# motordrive1.net
KiCad netlist of a schematic drawn in EAGLE
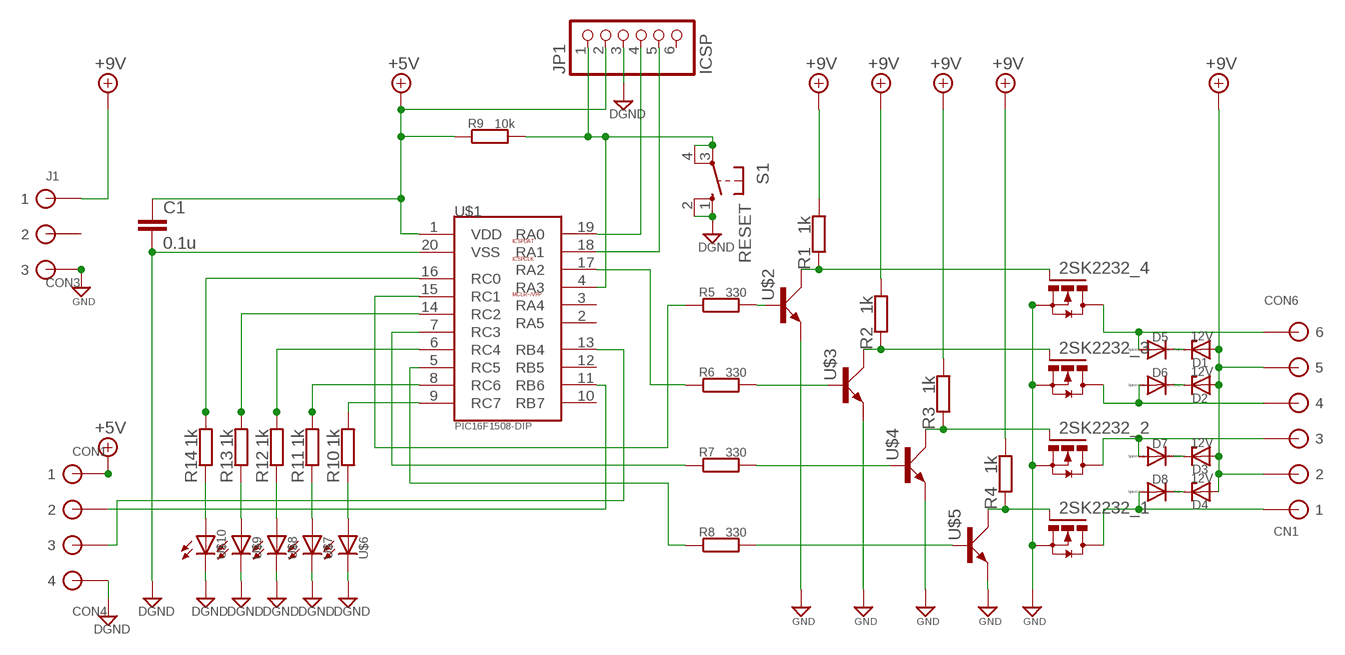
[diagram p0: schematic, sheet 1]

(export (version "E")
  (design (tool "Eeschema 10.0.6"))
  (components
    (comp (ref "2SK2232_1")
      (value "TO-220(MOS-FET_N)")
      (footprint "eagle-import:TO-220")
      (libsource (lib "eagle-import") (part "TO-220(MOS-FET_N)"))
    )
    (comp (ref "2SK2232_2")
      (value "TO-220(MOS-FET_N)")
      (footprint "eagle-import:TO-220")
      (libsource (lib "eagle-import") (part "TO-220(MOS-FET_N)"))
    )
    (comp (ref "2SK2232_3")
      (value "TO-220(MOS-FET_N)")
      (footprint "eagle-import:TO-220")
      (libsource (lib "eagle-import") (part "TO-220(MOS-FET_N)"))
    )
    (comp (ref "2SK2232_4")
      (value "TO-220(MOS-FET_N)")
      (footprint "eagle-import:TO-220")
      (libsource (lib "eagle-import") (part "TO-220(MOS-FET_N)"))
    )
    (comp (ref "C1")
      (value "0.1u")
      (footprint "eagle-import:C050-024X044")
      (libsource (lib "eagle-import") (part "コンデンサ(小型極性無し)050-024X044"))
    )
    (comp (ref "CN1")
      (value "CON6")
      (footprint "eagle-import:CON6")
      (libsource (lib "eagle-import") (part "CON6"))
    )
    (comp (ref "CON1")
      (value "CON4")
      (footprint "eagle-import:CON4")
      (libsource (lib "eagle-import") (part "CON4"))
    )
    (comp (ref "D1")
      (value "12V")
      (footprint "eagle-import:DO41Z(D=3)")
      (libsource (lib "eagle-import") (part "(汎用)ツェナーダイオードD=3"))
    )
    (comp (ref "D2")
      (value "12V")
      (footprint "eagle-import:DO41Z(D=3)")
      (libsource (lib "eagle-import") (part "(汎用)ツェナーダイオードD=3"))
    )
    (comp (ref "D3")
      (value "12V")
      (footprint "eagle-import:DO41Z(D=3)")
      (libsource (lib "eagle-import") (part "(汎用)ツェナーダイオードD=3"))
    )
    (comp (ref "D4")
      (value "12V")
      (footprint "eagle-import:DO41Z(D=3)")
      (libsource (lib "eagle-import") (part "(汎用)ツェナーダイオードD=3"))
    )
    (comp (ref "D5")
      (value "(汎用)D=3")
      (footprint "eagle-import:DO41(D=3)")
      (libsource (lib "eagle-import") (part "(汎用)D=3"))
    )
    (comp (ref "D6")
      (value "(汎用)D=3")
      (footprint "eagle-import:DO41(D=3)")
      (libsource (lib "eagle-import") (part "(汎用)D=3"))
    )
    (comp (ref "D7")
      (value "(汎用)D=3")
      (footprint "eagle-import:DO41(D=3)")
      (libsource (lib "eagle-import") (part "(汎用)D=3"))
    )
    (comp (ref "D8")
      (value "(汎用)D=3")
      (footprint "eagle-import:DO41(D=3)")
      (libsource (lib "eagle-import") (part "(汎用)D=3"))
    )
    (comp (ref "J1")
      (value "CON3")
      (footprint "eagle-import:CON3")
      (libsource (lib "eagle-import") (part "CON3"))
    )
    (comp (ref "JP1")
      (value "ICSP")
      (footprint "eagle-import:1X06")
      (libsource (lib "eagle-import") (part "PINHD-1X6"))
    )
    (comp (ref "R1")
      (value "1k")
      (footprint "eagle-import:0207_10")
      (libsource (lib "eagle-import") (part "抵抗(新JIS)0207/10"))
    )
    (comp (ref "R2")
      (value "1k")
      (footprint "eagle-import:0207_10")
      (libsource (lib "eagle-import") (part "抵抗(新JIS)0207/10"))
    )
    (comp (ref "R3")
      (value "1k")
      (footprint "eagle-import:0207_10")
      (libsource (lib "eagle-import") (part "抵抗(新JIS)0207/10"))
    )
    (comp (ref "R4")
      (value "1k")
      (footprint "eagle-import:0207_10")
      (libsource (lib "eagle-import") (part "抵抗(新JIS)0207/10"))
    )
    (comp (ref "R5")
      (value "330")
      (footprint "eagle-import:1_4W-H4_(0207_10)")
      (libsource (lib "eagle-import") (part "抵抗0207/10"))
    )
    (comp (ref "R6")
      (value "330")
      (footprint "eagle-import:1_4W-H4_(0207_10)")
      (libsource (lib "eagle-import") (part "抵抗0207/10"))
    )
    (comp (ref "R7")
      (value "330")
      (footprint "eagle-import:1_4W-H4_(0207_10)")
      (libsource (lib "eagle-import") (part "抵抗0207/10"))
    )
    (comp (ref "R8")
      (value "330")
      (footprint "eagle-import:1_4W-H4_(0207_10)")
      (libsource (lib "eagle-import") (part "抵抗0207/10"))
    )
    (comp (ref "R9")
      (value "10k")
      (footprint "eagle-import:1_4W-H4_(0207_10)")
      (libsource (lib "eagle-import") (part "抵抗0207/10"))
    )
    (comp (ref "R10")
      (value "1k")
      (footprint "eagle-import:0207_10")
      (libsource (lib "eagle-import") (part "抵抗(新JIS)0207/10"))
    )
    (comp (ref "R11")
      (value "1k")
      (footprint "eagle-import:0207_10")
      (libsource (lib "eagle-import") (part "抵抗(新JIS)0207/10"))
    )
    (comp (ref "R12")
      (value "1k")
      (footprint "eagle-import:0207_10")
      (libsource (lib "eagle-import") (part "抵抗(新JIS)0207/10"))
    )
    (comp (ref "R13")
      (value "1k")
      (footprint "eagle-import:0207_10")
      (libsource (lib "eagle-import") (part "抵抗(新JIS)0207/10"))
    )
    (comp (ref "R14")
      (value "1k")
      (footprint "eagle-import:0207_10")
      (libsource (lib "eagle-import") (part "抵抗(新JIS)0207/10"))
    )
    (comp (ref "S1")
      (value "RESET")
      (footprint "eagle-import:B3F-10XX")
      (fields (field (name "MPN") "B3F-1000"))
      (libsource (lib "eagle-import") (part "ノーマル4ピンタクトスイッチ"))
    )
    (comp (ref "U$1")
      (value "PIC16F1508-DIP")
      (footprint "eagle-import:DIP254P762X533-20")
      (libsource (lib "eagle-import") (part "PIC16F1508-DIP"))
    )
    (comp (ref "U$2")
      (value "TO-92(TRANSISTER_NPN)")
      (footprint "eagle-import:TO-92")
      (libsource (lib "eagle-import") (part "TO-92(TRANSISTER_NPN)"))
    )
    (comp (ref "U$3")
      (value "TO-92(TRANSISTER_NPN)")
      (footprint "eagle-import:TO-92")
      (libsource (lib "eagle-import") (part "TO-92(TRANSISTER_NPN)"))
    )
    (comp (ref "U$4")
      (value "TO-92(TRANSISTER_NPN)")
      (footprint "eagle-import:TO-92")
      (libsource (lib "eagle-import") (part "TO-92(TRANSISTER_NPN)"))
    )
    (comp (ref "U$5")
      (value "TO-92(TRANSISTER_NPN)")
      (footprint "eagle-import:TO-92")
      (libsource (lib "eagle-import") (part "TO-92(TRANSISTER_NPN)"))
    )
    (comp (ref "U$6")
      (value "LED(砲弾型)5")
      (footprint "eagle-import:LED5MM")
      (libsource (lib "eagle-import") (part "LED(砲弾型)5"))
    )
    (comp (ref "U$7")
      (value "LED(砲弾型)5")
      (footprint "eagle-import:LED5MM")
      (libsource (lib "eagle-import") (part "LED(砲弾型)5"))
    )
    (comp (ref "U$8")
      (value "LED(砲弾型)5")
      (footprint "eagle-import:LED5MM")
      (libsource (lib "eagle-import") (part "LED(砲弾型)5"))
    )
    (comp (ref "U$9")
      (value "LED(砲弾型)5")
      (footprint "eagle-import:LED5MM")
      (libsource (lib "eagle-import") (part "LED(砲弾型)5"))
    )
    (comp (ref "U$10")
      (value "LED(砲弾型)5")
      (footprint "eagle-import:LED5MM")
      (libsource (lib "eagle-import") (part "LED(砲弾型)5"))
    )
  )
  (nets
    (net (code "1") (name "+5V") (class "Default")
      (node (ref "C1") (pin "1") (pinfunction "1_1") (pintype "passive"))
      (node (ref "CON1") (pin "P$1") (pinfunction "1_P$1") (pintype "bidirectional"))
      (node (ref "JP1") (pin "2") (pinfunction "2_2") (pintype "passive"))
      (node (ref "R9") (pin "1") (pinfunction "1_1") (pintype "passive"))
      (node (ref "U$1") (pin "1") (pinfunction "VDD_1") (pintype "bidirectional"))
    )
    (net (code "2") (name "+9V") (class "Default")
      (node (ref "CN1") (pin "P$2") (pinfunction "2_P$2") (pintype "bidirectional"))
      (node (ref "CN1") (pin "P$5") (pinfunction "5_P$5") (pintype "bidirectional"))
      (node (ref "D1") (pin "A") (pinfunction "A_A") (pintype "passive"))
      (node (ref "D2") (pin "A") (pinfunction "A_A") (pintype "passive"))
      (node (ref "D3") (pin "A") (pinfunction "A_A") (pintype "passive"))
      (node (ref "D4") (pin "A") (pinfunction "A_A") (pintype "passive"))
      (node (ref "J1") (pin "P$1") (pinfunction "1_P$1") (pintype "bidirectional"))
      (node (ref "R1") (pin "2") (pinfunction "2_2") (pintype "passive"))
      (node (ref "R2") (pin "2") (pinfunction "2_2") (pintype "passive"))
      (node (ref "R3") (pin "2") (pinfunction "2_2") (pintype "passive"))
      (node (ref "R4") (pin "2") (pinfunction "2_2") (pintype "passive"))
    )
    (net (code "3") (name "DGND") (class "Default")
      (node (ref "C1") (pin "2") (pinfunction "2_2") (pintype "passive"))
      (node (ref "CON1") (pin "P$4") (pinfunction "4_P$4") (pintype "bidirectional"))
      (node (ref "JP1") (pin "3") (pinfunction "3_3") (pintype "passive"))
      (node (ref "S1") (pin "1") (pinfunction "S_1") (pintype "passive"))
      (node (ref "S1") (pin "2") (pinfunction "S1_2") (pintype "passive"))
      (node (ref "U$1") (pin "20") (pinfunction "VSS_20") (pintype "bidirectional"))
      (node (ref "U$10") (pin "K") (pinfunction "K_K") (pintype "passive"))
      (node (ref "U$6") (pin "K") (pinfunction "K_K") (pintype "passive"))
      (node (ref "U$7") (pin "K") (pinfunction "K_K") (pintype "passive"))
      (node (ref "U$8") (pin "K") (pinfunction "K_K") (pintype "passive"))
      (node (ref "U$9") (pin "K") (pinfunction "K_K") (pintype "passive"))
    )
    (net (code "4") (name "GND") (class "Default")
      (node (ref "2SK2232_1") (pin "3") (pinfunction "S_3") (pintype "passive"))
      (node (ref "2SK2232_2") (pin "3") (pinfunction "S_3") (pintype "passive"))
      (node (ref "2SK2232_3") (pin "3") (pinfunction "S_3") (pintype "passive"))
      (node (ref "2SK2232_4") (pin "3") (pinfunction "S_3") (pintype "passive"))
      (node (ref "J1") (pin "P$3") (pinfunction "3_P$3") (pintype "bidirectional"))
      (node (ref "U$2") (pin "1") (pinfunction "E_1") (pintype "passive"))
      (node (ref "U$3") (pin "1") (pinfunction "E_1") (pintype "passive"))
      (node (ref "U$4") (pin "1") (pinfunction "E_1") (pintype "passive"))
      (node (ref "U$5") (pin "1") (pinfunction "E_1") (pintype "passive"))
    )
    (net (code "5") (name "Net-(2SK2232_1-D)") (class "Default")
      (node (ref "2SK2232_1") (pin "2") (pinfunction "D_2") (pintype "passive"))
      (node (ref "CN1") (pin "P$1") (pinfunction "1_P$1") (pintype "bidirectional"))
      (node (ref "D8") (pin "A") (pinfunction "A_A") (pintype "passive"))
    )
    (net (code "6") (name "Net-(2SK2232_1-G)") (class "Default")
      (node (ref "2SK2232_1") (pin "1") (pinfunction "G_1") (pintype "passive"))
      (node (ref "R4") (pin "1") (pinfunction "1_1") (pintype "passive"))
      (node (ref "U$5") (pin "2") (pinfunction "C_2") (pintype "passive"))
    )
    (net (code "7") (name "Net-(2SK2232_2-D)") (class "Default")
      (node (ref "2SK2232_2") (pin "2") (pinfunction "D_2") (pintype "passive"))
      (node (ref "CN1") (pin "P$3") (pinfunction "3_P$3") (pintype "bidirectional"))
      (node (ref "D7") (pin "A") (pinfunction "A_A") (pintype "passive"))
    )
    (net (code "8") (name "Net-(2SK2232_2-G)") (class "Default")
      (node (ref "2SK2232_2") (pin "1") (pinfunction "G_1") (pintype "passive"))
      (node (ref "R3") (pin "1") (pinfunction "1_1") (pintype "passive"))
      (node (ref "U$4") (pin "2") (pinfunction "C_2") (pintype "passive"))
    )
    (net (code "9") (name "Net-(2SK2232_3-D)") (class "Default")
      (node (ref "2SK2232_3") (pin "2") (pinfunction "D_2") (pintype "passive"))
      (node (ref "CN1") (pin "P$4") (pinfunction "4_P$4") (pintype "bidirectional"))
      (node (ref "D6") (pin "A") (pinfunction "A_A") (pintype "passive"))
    )
    (net (code "10") (name "Net-(2SK2232_3-G)") (class "Default")
      (node (ref "2SK2232_3") (pin "1") (pinfunction "G_1") (pintype "passive"))
      (node (ref "R2") (pin "1") (pinfunction "1_1") (pintype "passive"))
      (node (ref "U$3") (pin "2") (pinfunction "C_2") (pintype "passive"))
    )
    (net (code "11") (name "Net-(2SK2232_4-D)") (class "Default")
      (node (ref "2SK2232_4") (pin "2") (pinfunction "D_2") (pintype "passive"))
      (node (ref "CN1") (pin "P$6") (pinfunction "6_P$6") (pintype "bidirectional"))
      (node (ref "D5") (pin "A") (pinfunction "A_A") (pintype "passive"))
    )
    (net (code "12") (name "Net-(2SK2232_4-G)") (class "Default")
      (node (ref "2SK2232_4") (pin "1") (pinfunction "G_1") (pintype "passive"))
      (node (ref "R1") (pin "1") (pinfunction "1_1") (pintype "passive"))
      (node (ref "U$2") (pin "2") (pinfunction "C_2") (pintype "passive"))
    )
    (net (code "13") (name "Net-(CON1-2)") (class "Default")
      (node (ref "CON1") (pin "P$2") (pinfunction "2_P$2") (pintype "bidirectional"))
      (node (ref "U$1") (pin "11") (pinfunction "RB6_11") (pintype "bidirectional"))
    )
    (net (code "14") (name "Net-(CON1-3)") (class "Default")
      (node (ref "CON1") (pin "P$3") (pinfunction "3_P$3") (pintype "bidirectional"))
      (node (ref "U$1") (pin "13") (pinfunction "RB4_13") (pintype "bidirectional"))
    )
    (net (code "15") (name "Net-(D1-PadC)") (class "Default")
      (node (ref "D1") (pin "C") (pinfunction "C_C") (pintype "passive"))
      (node (ref "D5") (pin "C") (pinfunction "C_C") (pintype "passive"))
    )
    (net (code "16") (name "Net-(D2-PadC)") (class "Default")
      (node (ref "D2") (pin "C") (pinfunction "C_C") (pintype "passive"))
      (node (ref "D6") (pin "C") (pinfunction "C_C") (pintype "passive"))
    )
    (net (code "17") (name "Net-(D3-PadC)") (class "Default")
      (node (ref "D3") (pin "C") (pinfunction "C_C") (pintype "passive"))
      (node (ref "D7") (pin "C") (pinfunction "C_C") (pintype "passive"))
    )
    (net (code "18") (name "Net-(D4-PadC)") (class "Default")
      (node (ref "D4") (pin "C") (pinfunction "C_C") (pintype "passive"))
      (node (ref "D8") (pin "C") (pinfunction "C_C") (pintype "passive"))
    )
    (net (code "19") (name "Net-(R10-Pad1)") (class "Default")
      (node (ref "R10") (pin "1") (pinfunction "1_1") (pintype "passive"))
      (node (ref "U$6") (pin "A") (pinfunction "A_A") (pintype "passive"))
    )
    (net (code "20") (name "Net-(R11-Pad1)") (class "Default")
      (node (ref "R11") (pin "1") (pinfunction "1_1") (pintype "passive"))
      (node (ref "U$7") (pin "A") (pinfunction "A_A") (pintype "passive"))
    )
    (net (code "21") (name "Net-(R12-Pad1)") (class "Default")
      (node (ref "R12") (pin "1") (pinfunction "1_1") (pintype "passive"))
      (node (ref "U$8") (pin "A") (pinfunction "A_A") (pintype "passive"))
    )
    (net (code "22") (name "Net-(R13-Pad1)") (class "Default")
      (node (ref "R13") (pin "1") (pinfunction "1_1") (pintype "passive"))
      (node (ref "U$9") (pin "A") (pinfunction "A_A") (pintype "passive"))
    )
    (net (code "23") (name "Net-(R14-Pad1)") (class "Default")
      (node (ref "R14") (pin "1") (pinfunction "1_1") (pintype "passive"))
      (node (ref "U$10") (pin "A") (pinfunction "A_A") (pintype "passive"))
    )
    (net (code "24") (name "Net-(S1-P)") (class "Default")
      (node (ref "JP1") (pin "1") (pinfunction "1_1") (pintype "passive"))
      (node (ref "R9") (pin "2") (pinfunction "2_2") (pintype "passive"))
      (node (ref "S1") (pin "3") (pinfunction "P_3") (pintype "passive"))
      (node (ref "S1") (pin "4") (pinfunction "P1_4") (pintype "passive"))
      (node (ref "U$1") (pin "4") (pinfunction "RA3_4") (pintype "bidirectional"))
    )
    (net (code "25") (name "Net-(U$1-RA0)") (class "Default")
      (node (ref "JP1") (pin "4") (pinfunction "4_4") (pintype "passive"))
      (node (ref "U$1") (pin "19") (pinfunction "RA0_19") (pintype "bidirectional"))
    )
    (net (code "26") (name "Net-(U$1-RA1)") (class "Default")
      (node (ref "JP1") (pin "5") (pinfunction "5_5") (pintype "passive"))
      (node (ref "U$1") (pin "18") (pinfunction "RA1_18") (pintype "bidirectional"))
    )
    (net (code "27") (name "Net-(U$1-RA2)") (class "Default")
      (node (ref "R6") (pin "1") (pinfunction "1_1") (pintype "passive"))
      (node (ref "U$1") (pin "17") (pinfunction "RA2_17") (pintype "bidirectional"))
    )
    (net (code "28") (name "Net-(U$1-RC0)") (class "Default")
      (node (ref "R14") (pin "2") (pinfunction "2_2") (pintype "passive"))
      (node (ref "U$1") (pin "16") (pinfunction "RC0_16") (pintype "bidirectional"))
    )
    (net (code "29") (name "Net-(U$1-RC1)") (class "Default")
      (node (ref "R5") (pin "1") (pinfunction "1_1") (pintype "passive"))
      (node (ref "U$1") (pin "15") (pinfunction "RC1_15") (pintype "bidirectional"))
    )
    (net (code "30") (name "Net-(U$1-RC2)") (class "Default")
      (node (ref "R13") (pin "2") (pinfunction "2_2") (pintype "passive"))
      (node (ref "U$1") (pin "14") (pinfunction "RC2_14") (pintype "bidirectional"))
    )
    (net (code "31") (name "Net-(U$1-RC3)") (class "Default")
      (node (ref "R7") (pin "1") (pinfunction "1_1") (pintype "passive"))
      (node (ref "U$1") (pin "7") (pinfunction "RC3_7") (pintype "bidirectional"))
    )
    (net (code "32") (name "Net-(U$1-RC4)") (class "Default")
      (node (ref "R12") (pin "2") (pinfunction "2_2") (pintype "passive"))
      (node (ref "U$1") (pin "6") (pinfunction "RC4_6") (pintype "bidirectional"))
    )
    (net (code "33") (name "Net-(U$1-RC5)") (class "Default")
      (node (ref "R8") (pin "1") (pinfunction "1_1") (pintype "passive"))
      (node (ref "U$1") (pin "5") (pinfunction "RC5_5") (pintype "bidirectional"))
    )
    (net (code "34") (name "Net-(U$1-RC6)") (class "Default")
      (node (ref "R11") (pin "2") (pinfunction "2_2") (pintype "passive"))
      (node (ref "U$1") (pin "8") (pinfunction "RC6_8") (pintype "bidirectional"))
    )
    (net (code "35") (name "Net-(U$1-RC7)") (class "Default")
      (node (ref "R10") (pin "2") (pinfunction "2_2") (pintype "passive"))
      (node (ref "U$1") (pin "9") (pinfunction "RC7_9") (pintype "bidirectional"))
    )
    (net (code "36") (name "Net-(U$2-B)") (class "Default")
      (node (ref "R5") (pin "2") (pinfunction "2_2") (pintype "passive"))
      (node (ref "U$2") (pin "3") (pinfunction "B_3") (pintype "passive"))
    )
    (net (code "37") (name "Net-(U$3-B)") (class "Default")
      (node (ref "R6") (pin "2") (pinfunction "2_2") (pintype "passive"))
      (node (ref "U$3") (pin "3") (pinfunction "B_3") (pintype "passive"))
    )
    (net (code "38") (name "Net-(U$4-B)") (class "Default")
      (node (ref "R7") (pin "2") (pinfunction "2_2") (pintype "passive"))
      (node (ref "U$4") (pin "3") (pinfunction "B_3") (pintype "passive"))
    )
    (net (code "39") (name "Net-(U$5-B)") (class "Default")
      (node (ref "R8") (pin "2") (pinfunction "2_2") (pintype "passive"))
      (node (ref "U$5") (pin "3") (pinfunction "B_3") (pintype "passive"))
    )
    (net (code "40") (name "unconnected-(J1-2-PadP$2)") (class "Default")
      (node (ref "J1") (pin "P$2") (pinfunction "2_P$2") (pintype "bidirectional"))
    )
    (net (code "41") (name "unconnected-(JP1-Pad6)") (class "Default")
      (node (ref "JP1") (pin "6") (pinfunction "6_6") (pintype "passive"))
    )
    (net (code "42") (name "unconnected-(U$1-RA4-Pad3)") (class "Default")
      (node (ref "U$1") (pin "3") (pinfunction "RA4_3") (pintype "bidirectional"))
    )
    (net (code "43") (name "unconnected-(U$1-RA5-Pad2)") (class "Default")
      (node (ref "U$1") (pin "2") (pinfunction "RA5_2") (pintype "bidirectional"))
    )
    (net (code "44") (name "unconnected-(U$1-RB5-Pad12)") (class "Default")
      (node (ref "U$1") (pin "12") (pinfunction "RB5_12") (pintype "bidirectional"))
    )
    (net (code "45") (name "unconnected-(U$1-RB7-Pad10)") (class "Default")
      (node (ref "U$1") (pin "10") (pinfunction "RB7_10") (pintype "bidirectional"))
    )
  )
)
